# PPSB-TH.net
KiCad netlist of a schematic drawn in EAGLE
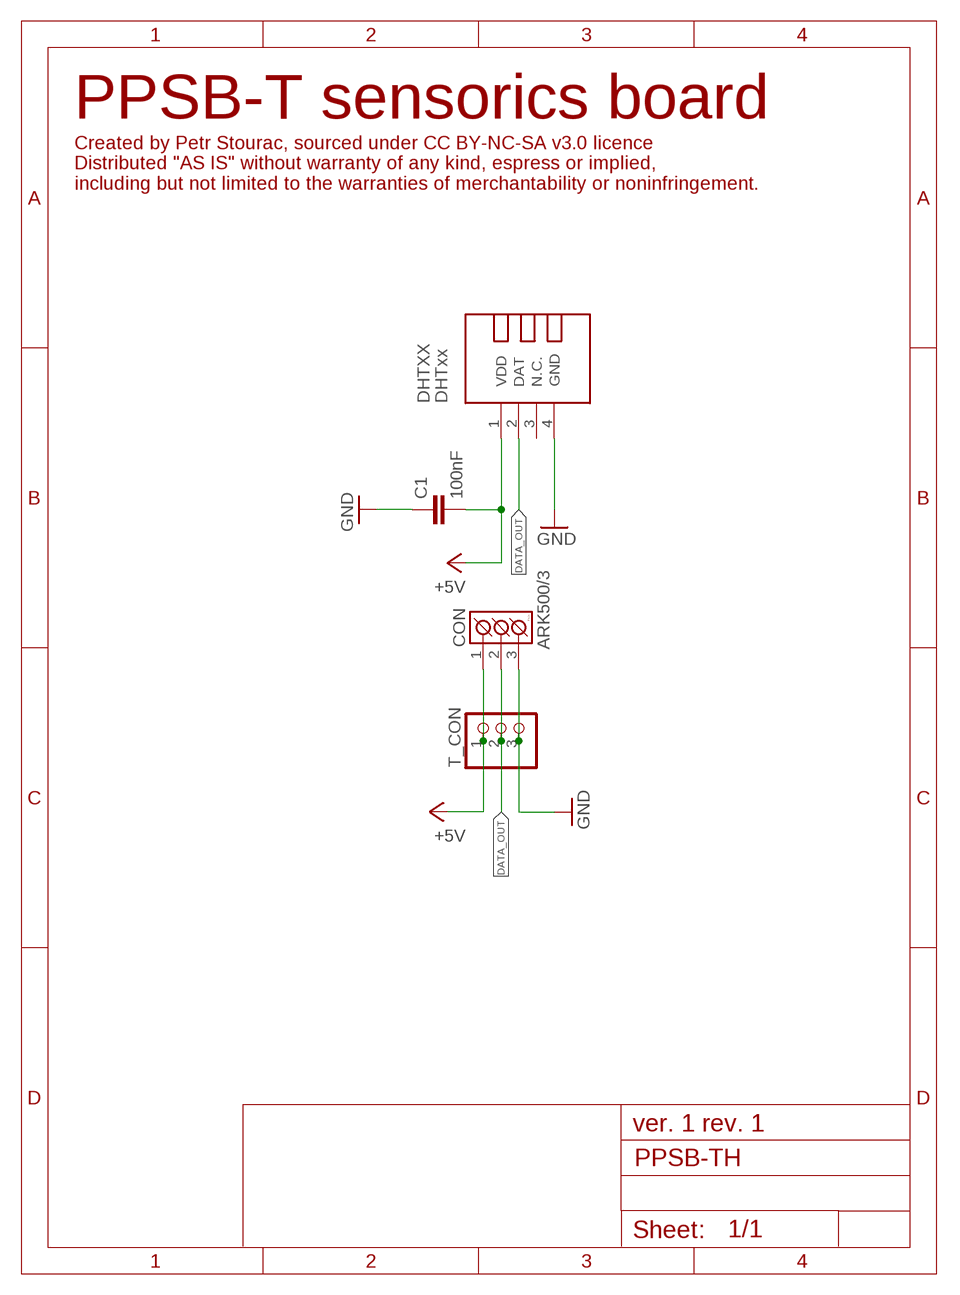
[diagram p0: schematic, sheet 1]

(export (version "E")
  (design (tool "Eeschema 10.0.6"))
  (components
    (comp (ref "C1")
      (value "100nF")
      (footprint "eagle-import:C0603")
      (libsource (lib "eagle-import") (part "C-EUC0603"))
    )
    (comp (ref "CON")
      (value "ARK500/3")
      (footprint "eagle-import:ARK500_3")
      (libsource (lib "eagle-import") (part "ARK500/3"))
    )
    (comp (ref "DHTXX")
      (value "DHTxx")
      (footprint "eagle-import:TEMP-HUM-SENSOR-DHT22")
      (libsource (lib "eagle-import") (part "TEMP-HUM-SENSOR-DHT22"))
    )
    (comp (ref "T_CON")
      (value "PINHD-1X3")
      (footprint "eagle-import:1X03")
      (libsource (lib "eagle-import") (part "PINHD-1X3"))
    )
  )
  (nets
    (net (code "1") (name "+5V") (class "Default")
      (node (ref "C1") (pin "2") (pinfunction "2_2") (pintype "passive"))
      (node (ref "CON") (pin "1") (pinfunction "K1_1") (pintype "passive"))
      (node (ref "DHTXX") (pin "1") (pinfunction "VDD_1") (pintype "power_in"))
      (node (ref "T_CON") (pin "1") (pinfunction "1_1") (pintype "passive"))
    )
    (net (code "2") (name "DATA_OUT") (class "Default")
      (node (ref "CON") (pin "2") (pinfunction "K2_2") (pintype "passive"))
      (node (ref "DHTXX") (pin "2") (pinfunction "DAT_2") (pintype "bidirectional"))
      (node (ref "T_CON") (pin "2") (pinfunction "2_2") (pintype "passive"))
    )
    (net (code "3") (name "GND") (class "Default")
      (node (ref "C1") (pin "1") (pinfunction "1_1") (pintype "passive"))
      (node (ref "CON") (pin "3") (pinfunction "K3_3") (pintype "passive"))
      (node (ref "DHTXX") (pin "4") (pinfunction "GND_4") (pintype "power_in"))
      (node (ref "T_CON") (pin "3") (pinfunction "3_3") (pintype "passive"))
    )
    (net (code "4") (name "unconnected-(DHTXX-N.C.-Pad3)") (class "Default")
      (node (ref "DHTXX") (pin "3") (pinfunction "N.C._3") (pintype "passive"))
    )
  )
)
